# CHILD_BOARD.net
KiCad netlist of a schematic drawn in Altium Designer
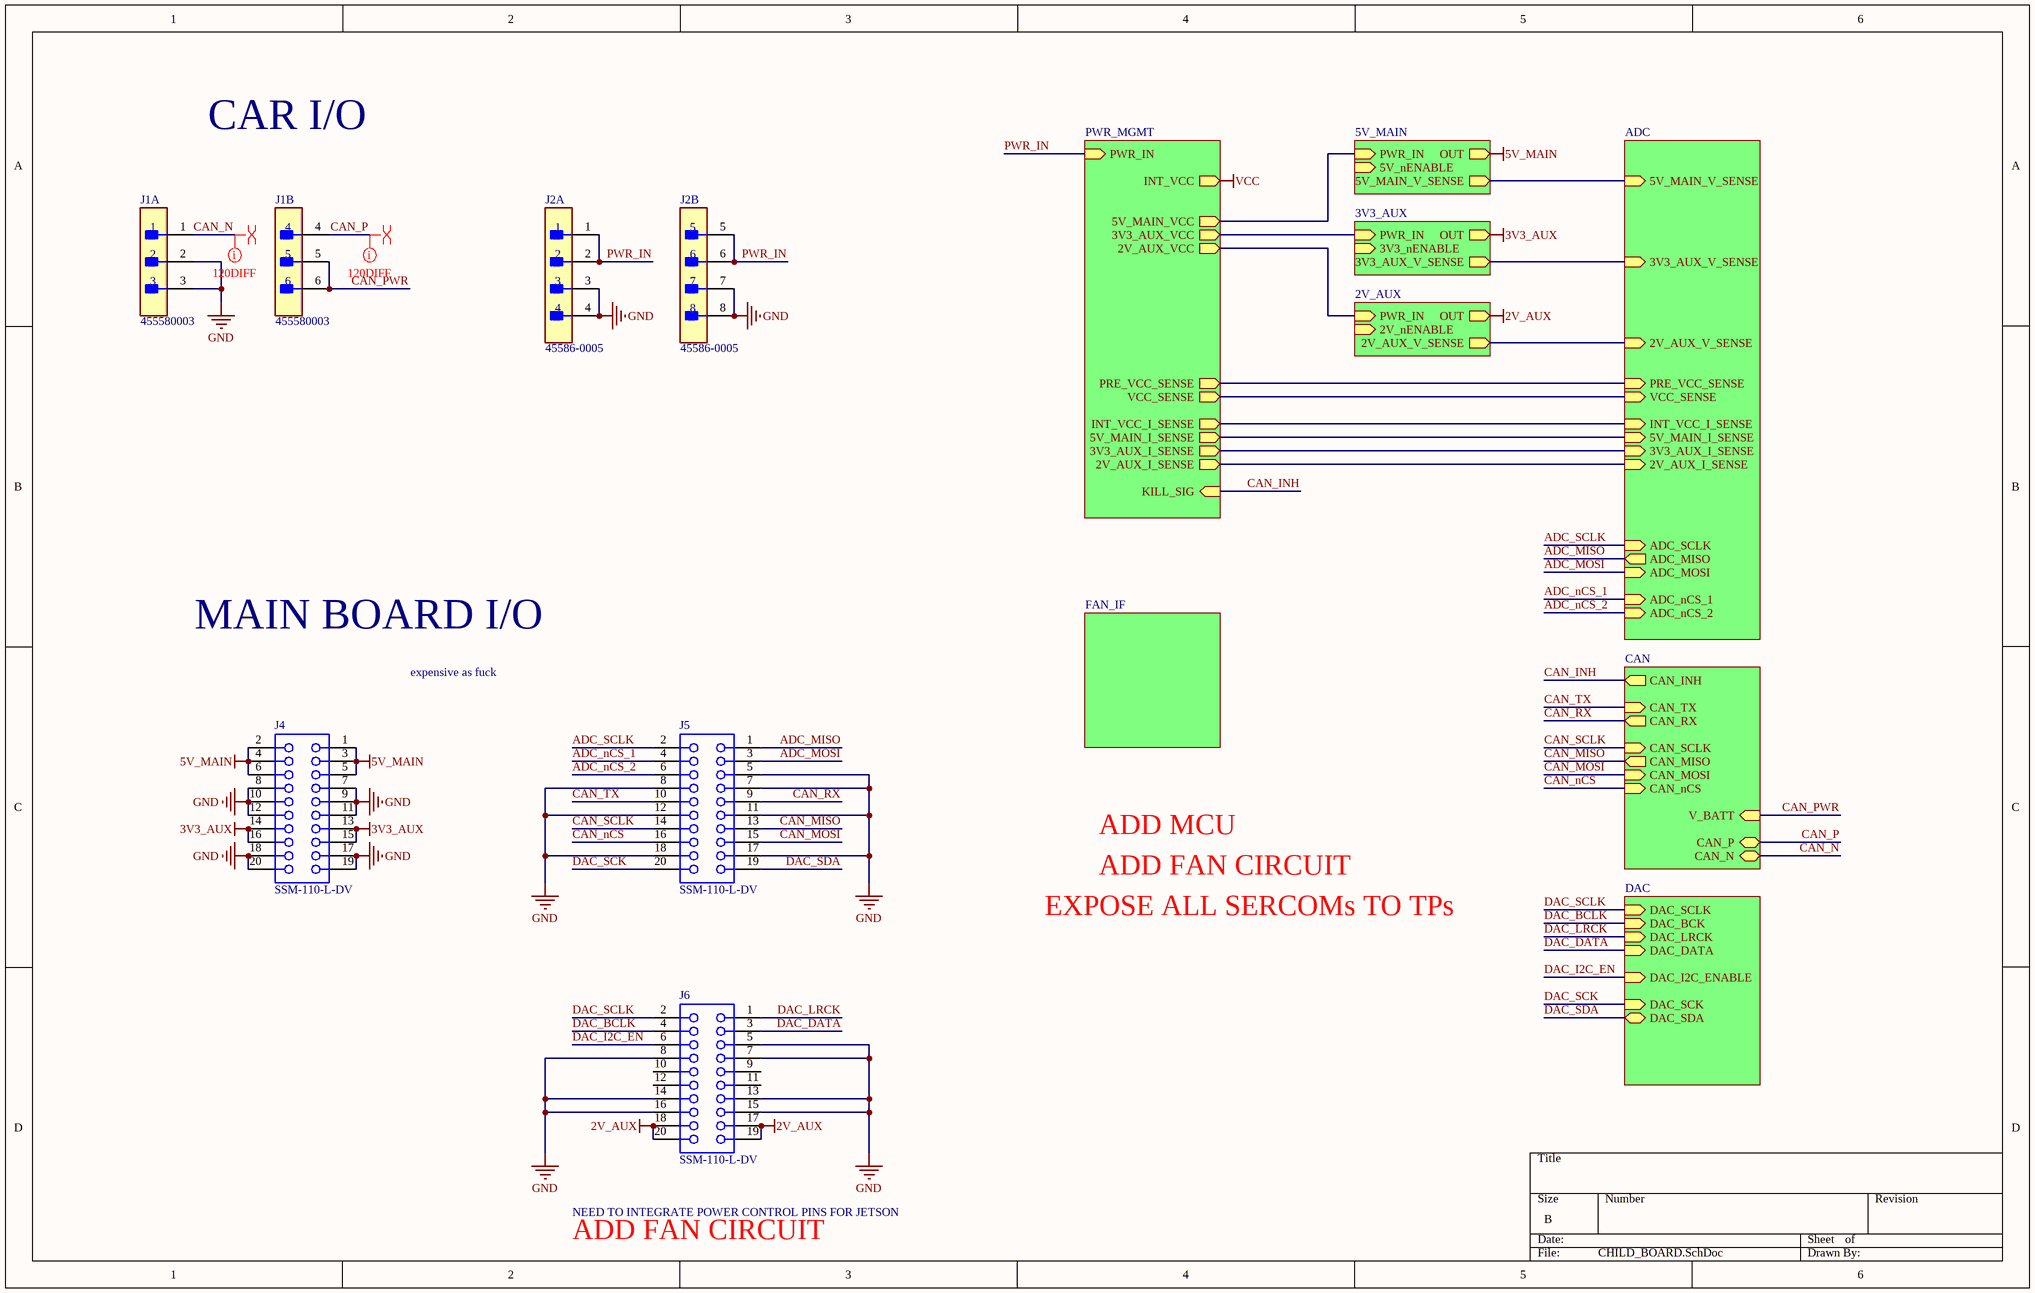
[diagram p0: CHILD_BOARD.SchDoc]

(export (version "E")
  (design (tool "Eeschema 10.0.6"))
  (components
    (comp (ref "J1")
      (value "455580003")
      (footprint "FP-455580003-MFG")
      (description "CONN HEADER R/A 6POS 4.2MM")
      (fields
        (field (name "OCTOPART") "https://octopart.com/45558-0003-molex-7672845")
        (field (name "MANUFACTURER") "Molex")
      )
      (libsource (lib "Altium Content Vault") (part "bb9cbdb24149a20ba329b4e86909569"))
    )
    (comp (ref "J2")
      (value "45586-0005")
      (footprint "FP-45586-0005-MFG")
      (description "CONN HEADER R/A 8POS 4.2MM")
      (libsource (lib "Altium Content Vault") (part "85438c39ca9ef07d43bb2e97c52bc44"))
    )
    (comp (ref "J4")
      (value "SSM-110-L-DV")
      (footprint "SMTC-SSM-110-X-DV")
      (fields (field (name "MANUFACTURER") "Samtec"))
      (libsource (lib "Altium Content Vault") (part "SMTC-SSM-110-X-DV"))
    )
    (comp (ref "J5")
      (value "SSM-110-L-DV")
      (footprint "SMTC-SSM-110-X-DV")
      (fields (field (name "MANUFACTURER") "Samtec"))
      (libsource (lib "Altium Content Vault") (part "SMTC-SSM-110-X-DV"))
    )
    (comp (ref "J6")
      (value "SSM-110-L-DV")
      (footprint "SMTC-SSM-110-X-DV")
      (fields (field (name "MANUFACTURER") "Samtec"))
      (libsource (lib "Altium Content Vault") (part "SMTC-SSM-110-X-DV"))
    )
  )
  (nets
    (net (code "13") (name "/ADC_MISO") (class "Default")
      (node (ref "J5") (pin "1") (pinfunction "1_1") (pintype "passive"))
    )
    (net (code "14") (name "/ADC_MOSI") (class "Default")
      (node (ref "J5") (pin "3") (pinfunction "3_3") (pintype "passive"))
    )
    (net (code "15") (name "/ADC_SCLK") (class "Default")
      (node (ref "J5") (pin "2") (pinfunction "2_2") (pintype "passive"))
    )
    (net (code "16") (name "/ADC_nCS_1") (class "Default")
      (node (ref "J5") (pin "4") (pinfunction "4_4") (pintype "passive"))
    )
    (net (code "17") (name "/ADC_nCS_2") (class "Default")
      (node (ref "J5") (pin "6") (pinfunction "6_6") (pintype "passive"))
    )
    (net (code "19") (name "/CAN_MISO") (class "Default")
      (node (ref "J5") (pin "13") (pinfunction "13_13") (pintype "passive"))
    )
    (net (code "20") (name "/CAN_MOSI") (class "Default")
      (node (ref "J5") (pin "15") (pinfunction "15_15") (pintype "passive"))
    )
    (net (code "21") (name "/CAN_N") (class "Default")
      (node (ref "J1") (pin "1") (pinfunction "1_1") (pintype "passive"))
    )
    (net (code "22") (name "/CAN_P") (class "Default")
      (node (ref "J1") (pin "4") (pinfunction "4_4") (pintype "passive"))
    )
    (net (code "23") (name "/CAN_PWR") (class "Default")
      (node (ref "J1") (pin "5") (pinfunction "5_5") (pintype "passive"))
      (node (ref "J1") (pin "6") (pinfunction "6_6") (pintype "passive"))
    )
    (net (code "24") (name "/CAN_RX") (class "Default")
      (node (ref "J5") (pin "9") (pinfunction "9_9") (pintype "passive"))
    )
    (net (code "25") (name "/CAN_SCLK") (class "Default")
      (node (ref "J5") (pin "14") (pinfunction "14_14") (pintype "passive"))
    )
    (net (code "26") (name "/CAN_TX") (class "Default")
      (node (ref "J5") (pin "10") (pinfunction "10_10") (pintype "passive"))
    )
    (net (code "27") (name "/CAN_nCS") (class "Default")
      (node (ref "J5") (pin "16") (pinfunction "16_16") (pintype "passive"))
    )
    (net (code "28") (name "/DAC_BCLK") (class "Default")
      (node (ref "J6") (pin "4") (pinfunction "4_4") (pintype "passive"))
    )
    (net (code "29") (name "/DAC_DATA") (class "Default")
      (node (ref "J6") (pin "3") (pinfunction "3_3") (pintype "passive"))
    )
    (net (code "30") (name "/DAC_I2C_EN") (class "Default")
      (node (ref "J6") (pin "6") (pinfunction "6_6") (pintype "passive"))
    )
    (net (code "31") (name "/DAC_LRCK") (class "Default")
      (node (ref "J6") (pin "1") (pinfunction "1_1") (pintype "passive"))
    )
    (net (code "32") (name "/DAC_SCK") (class "Default")
      (node (ref "J5") (pin "20") (pinfunction "20_20") (pintype "passive"))
    )
    (net (code "33") (name "/DAC_SCLK") (class "Default")
      (node (ref "J6") (pin "2") (pinfunction "2_2") (pintype "passive"))
    )
    (net (code "34") (name "/DAC_SDA") (class "Default")
      (node (ref "J5") (pin "19") (pinfunction "19_19") (pintype "passive"))
    )
    (net (code "37") (name "/PWR_IN") (class "Default")
      (node (ref "J2") (pin "1") (pinfunction "1_1") (pintype "passive"))
      (node (ref "J2") (pin "2") (pinfunction "2_2") (pintype "passive"))
      (node (ref "J2") (pin "5") (pinfunction "5_5") (pintype "passive"))
      (node (ref "J2") (pin "6") (pinfunction "6_6") (pintype "passive"))
    )
    (net (code "39") (name "2V_AUX") (class "Default")
      (node (ref "J6") (pin "17") (pinfunction "17_17") (pintype "passive"))
      (node (ref "J6") (pin "18") (pinfunction "18_18") (pintype "passive"))
      (node (ref "J6") (pin "19") (pinfunction "19_19") (pintype "passive"))
      (node (ref "J6") (pin "20") (pinfunction "20_20") (pintype "passive"))
    )
    (net (code "40") (name "3V3_AUX") (class "Default")
      (node (ref "J4") (pin "13") (pinfunction "13_13") (pintype "passive"))
      (node (ref "J4") (pin "14") (pinfunction "14_14") (pintype "passive"))
      (node (ref "J4") (pin "15") (pinfunction "15_15") (pintype "passive"))
      (node (ref "J4") (pin "16") (pinfunction "16_16") (pintype "passive"))
    )
    (net (code "41") (name "5V_MAIN") (class "Default")
      (node (ref "J4") (pin "1") (pinfunction "1_1") (pintype "passive"))
      (node (ref "J4") (pin "2") (pinfunction "2_2") (pintype "passive"))
      (node (ref "J4") (pin "3") (pinfunction "3_3") (pintype "passive"))
      (node (ref "J4") (pin "4") (pinfunction "4_4") (pintype "passive"))
      (node (ref "J4") (pin "5") (pinfunction "5_5") (pintype "passive"))
      (node (ref "J4") (pin "6") (pinfunction "6_6") (pintype "passive"))
    )
    (net (code "42") (name "GND") (class "Default")
      (node (ref "J1") (pin "2") (pinfunction "2_2") (pintype "passive"))
      (node (ref "J1") (pin "3") (pinfunction "3_3") (pintype "passive"))
      (node (ref "J2") (pin "3") (pinfunction "3_3") (pintype "passive"))
      (node (ref "J2") (pin "4") (pinfunction "4_4") (pintype "passive"))
      (node (ref "J2") (pin "7") (pinfunction "7_7") (pintype "passive"))
      (node (ref "J2") (pin "8") (pinfunction "8_8") (pintype "passive"))
      (node (ref "J4") (pin "10") (pinfunction "10_10") (pintype "passive"))
      (node (ref "J4") (pin "11") (pinfunction "11_11") (pintype "passive"))
      (node (ref "J4") (pin "12") (pinfunction "12_12") (pintype "passive"))
      (node (ref "J4") (pin "17") (pinfunction "17_17") (pintype "passive"))
      (node (ref "J4") (pin "18") (pinfunction "18_18") (pintype "passive"))
      (node (ref "J4") (pin "19") (pinfunction "19_19") (pintype "passive"))
      (node (ref "J4") (pin "20") (pinfunction "20_20") (pintype "passive"))
      (node (ref "J4") (pin "7") (pinfunction "7_7") (pintype "passive"))
      (node (ref "J4") (pin "8") (pinfunction "8_8") (pintype "passive"))
      (node (ref "J4") (pin "9") (pinfunction "9_9") (pintype "passive"))
      (node (ref "J5") (pin "11") (pinfunction "11_11") (pintype "passive"))
      (node (ref "J5") (pin "12") (pinfunction "12_12") (pintype "passive"))
      (node (ref "J5") (pin "17") (pinfunction "17_17") (pintype "passive"))
      (node (ref "J5") (pin "18") (pinfunction "18_18") (pintype "passive"))
      (node (ref "J5") (pin "5") (pinfunction "5_5") (pintype "passive"))
      (node (ref "J5") (pin "7") (pinfunction "7_7") (pintype "passive"))
      (node (ref "J5") (pin "8") (pinfunction "8_8") (pintype "passive"))
      (node (ref "J6") (pin "13") (pinfunction "13_13") (pintype "passive"))
      (node (ref "J6") (pin "14") (pinfunction "14_14") (pintype "passive"))
      (node (ref "J6") (pin "15") (pinfunction "15_15") (pintype "passive"))
      (node (ref "J6") (pin "16") (pinfunction "16_16") (pintype "passive"))
      (node (ref "J6") (pin "5") (pinfunction "5_5") (pintype "passive"))
      (node (ref "J6") (pin "7") (pinfunction "7_7") (pintype "passive"))
      (node (ref "J6") (pin "8") (pinfunction "8_8") (pintype "passive"))
    )
    (net (code "44") (name "unconnected-(J6-Pad9)") (class "Default")
      (node (ref "J6") (pin "9") (pinfunction "9_9") (pintype "passive"))
    )
    (net (code "45") (name "unconnected-(J6-Pad10)") (class "Default")
      (node (ref "J6") (pin "10") (pinfunction "10_10") (pintype "passive"))
    )
    (net (code "46") (name "unconnected-(J6-Pad11)") (class "Default")
      (node (ref "J6") (pin "11") (pinfunction "11_11") (pintype "passive"))
    )
    (net (code "47") (name "unconnected-(J6-Pad12)") (class "Default")
      (node (ref "J6") (pin "12") (pinfunction "12_12") (pintype "passive"))
    )
  )
)
